# panel-mount-orafice-mk-2_0.net
KiCad netlist of a schematic drawn in EAGLE
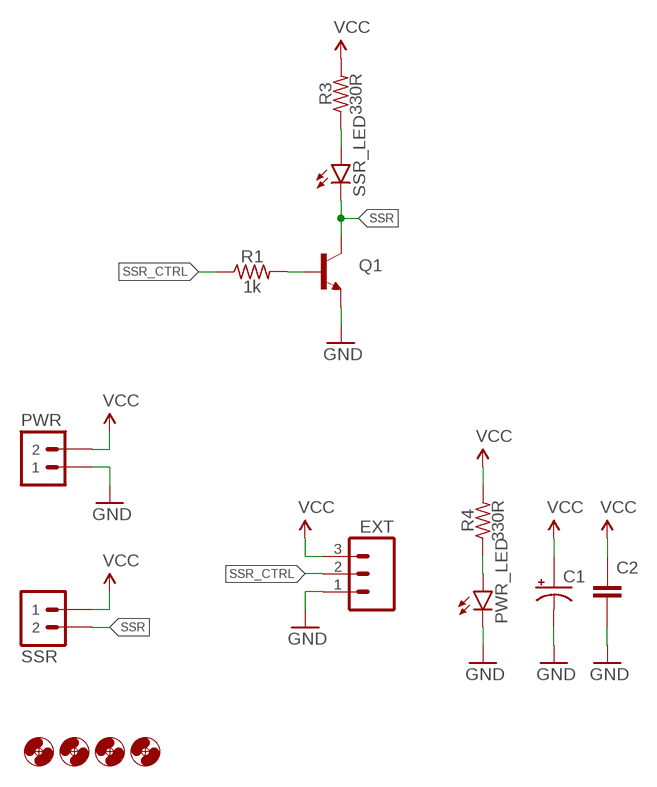
[diagram p0: schematic, sheet 1]

(export (version "E")
  (design (tool "Eeschema 10.0.6"))
  (components
    (comp (ref "C1")
      (value "CAPACITOR-POLARIZEDE3.5-8")
      (footprint "eagle-import:E3,5-8")
      (libsource (lib "eagle-import") (part "CAPACITOR-POLARIZEDE3.5-8"))
    )
    (comp (ref "C2")
      (value "CAPACITOR-CERAMIC025-024X044")
      (footprint "eagle-import:C025-024X044")
      (libsource (lib "eagle-import") (part "CAPACITOR-CERAMIC025-024X044"))
    )
    (comp (ref "EXT")
      (value "M03JST-XH-RA-PTH")
      (footprint "eagle-import:JST-3-XH-RA-PTH")
      (libsource (lib "eagle-import") (part "M03JST-XH-RA-PTH"))
    )
    (comp (ref "H1")
      (value "HOLE#2")
      (footprint "eagle-import:HOLE-#2")
      (libsource (lib "eagle-import") (part "HOLE#2"))
    )
    (comp (ref "H2")
      (value "HOLE#2")
      (footprint "eagle-import:HOLE-#2")
      (libsource (lib "eagle-import") (part "HOLE#2"))
    )
    (comp (ref "H3")
      (value "HOLE#2")
      (footprint "eagle-import:HOLE-#2")
      (libsource (lib "eagle-import") (part "HOLE#2"))
    )
    (comp (ref "H4")
      (value "HOLE#2")
      (footprint "eagle-import:HOLE-#2")
      (libsource (lib "eagle-import") (part "HOLE#2"))
    )
    (comp (ref "PWR")
      (value "M02JST-PTH-VERT")
      (footprint "eagle-import:JST-2-PH-VERT-PTH")
      (libsource (lib "eagle-import") (part "M02JST-PTH-VERT"))
    )
    (comp (ref "PWR_LED")
      (value "LED3MM")
      (footprint "eagle-import:LED3MM")
      (libsource (lib "eagle-import") (part "LED3MM"))
    )
    (comp (ref "Q1")
      (value "TRANSISTOR_NPNTO-92-AMMO-EBC")
      (footprint "eagle-import:TO-92-AMMO")
      (libsource (lib "eagle-import") (part "TRANSISTOR_NPNTO-92-AMMO-EBC"))
    )
    (comp (ref "R1")
      (value "1k")
      (footprint "eagle-import:RESISTOR-AXIAL-PTH-6.35MM")
      (libsource (lib "eagle-import") (part "RESISTORPTH-AXIAL-6.35MM"))
    )
    (comp (ref "R3")
      (value "330R")
      (footprint "eagle-import:RESISTOR-AXIAL-PTH-6.35MM")
      (libsource (lib "eagle-import") (part "RESISTORPTH-AXIAL-6.35MM"))
    )
    (comp (ref "R4")
      (value "330R")
      (footprint "eagle-import:RESISTOR-AXIAL-PTH-6.35MM")
      (libsource (lib "eagle-import") (part "RESISTORPTH-AXIAL-6.35MM"))
    )
    (comp (ref "SSR")
      (value "M02JST-PTH-VERT")
      (footprint "eagle-import:JST-2-PH-VERT-PTH")
      (libsource (lib "eagle-import") (part "M02JST-PTH-VERT"))
    )
    (comp (ref "SSR_LED")
      (value "LED3MM")
      (footprint "eagle-import:LED3MM")
      (libsource (lib "eagle-import") (part "LED3MM"))
    )
  )
  (nets
    (net (code "1") (name "GND") (class "Default")
      (node (ref "C1") (pin "-") (pinfunction "-_-") (pintype "passive"))
      (node (ref "C2") (pin "2") (pinfunction "2_2") (pintype "passive"))
      (node (ref "EXT") (pin "1") (pinfunction "1_1") (pintype "passive"))
      (node (ref "PWR") (pin "1") (pinfunction "1_1") (pintype "passive"))
      (node (ref "PWR_LED") (pin "K") (pinfunction "C_K") (pintype "passive"))
      (node (ref "Q1") (pin "1") (pinfunction "E_1") (pintype "passive"))
    )
    (net (code "2") (name "Net-(Q1-B)") (class "Default")
      (node (ref "Q1") (pin "2") (pinfunction "B_2") (pintype "passive"))
      (node (ref "R1") (pin "P$2") (pinfunction "2_P$2") (pintype "passive"))
    )
    (net (code "3") (name "Net-(R3-1)") (class "Default")
      (node (ref "R3") (pin "P$1") (pinfunction "1_P$1") (pintype "passive"))
      (node (ref "SSR_LED") (pin "A") (pinfunction "A_A") (pintype "passive"))
    )
    (net (code "4") (name "Net-(R4-1)") (class "Default")
      (node (ref "PWR_LED") (pin "A") (pinfunction "A_A") (pintype "passive"))
      (node (ref "R4") (pin "P$1") (pinfunction "1_P$1") (pintype "passive"))
    )
    (net (code "5") (name "SSR") (class "Default")
      (node (ref "Q1") (pin "3") (pinfunction "C_3") (pintype "passive"))
      (node (ref "SSR") (pin "2") (pinfunction "2_2") (pintype "passive"))
      (node (ref "SSR_LED") (pin "K") (pinfunction "C_K") (pintype "passive"))
    )
    (net (code "6") (name "SSR_CTRL") (class "Default")
      (node (ref "EXT") (pin "2") (pinfunction "2_2") (pintype "passive"))
      (node (ref "R1") (pin "P$1") (pinfunction "1_P$1") (pintype "passive"))
    )
    (net (code "7") (name "VCC") (class "Default")
      (node (ref "C1") (pin "+") (pinfunction "+_+") (pintype "passive"))
      (node (ref "C2") (pin "1") (pinfunction "1_1") (pintype "passive"))
      (node (ref "EXT") (pin "3") (pinfunction "3_3") (pintype "passive"))
      (node (ref "PWR") (pin "2") (pinfunction "2_2") (pintype "passive"))
      (node (ref "R3") (pin "P$2") (pinfunction "2_P$2") (pintype "passive"))
      (node (ref "R4") (pin "P$2") (pinfunction "2_P$2") (pintype "passive"))
      (node (ref "SSR") (pin "1") (pinfunction "1_1") (pintype "passive"))
    )
  )
)
